# Motors.net
KiCad netlist of a schematic drawn in Altium Designer
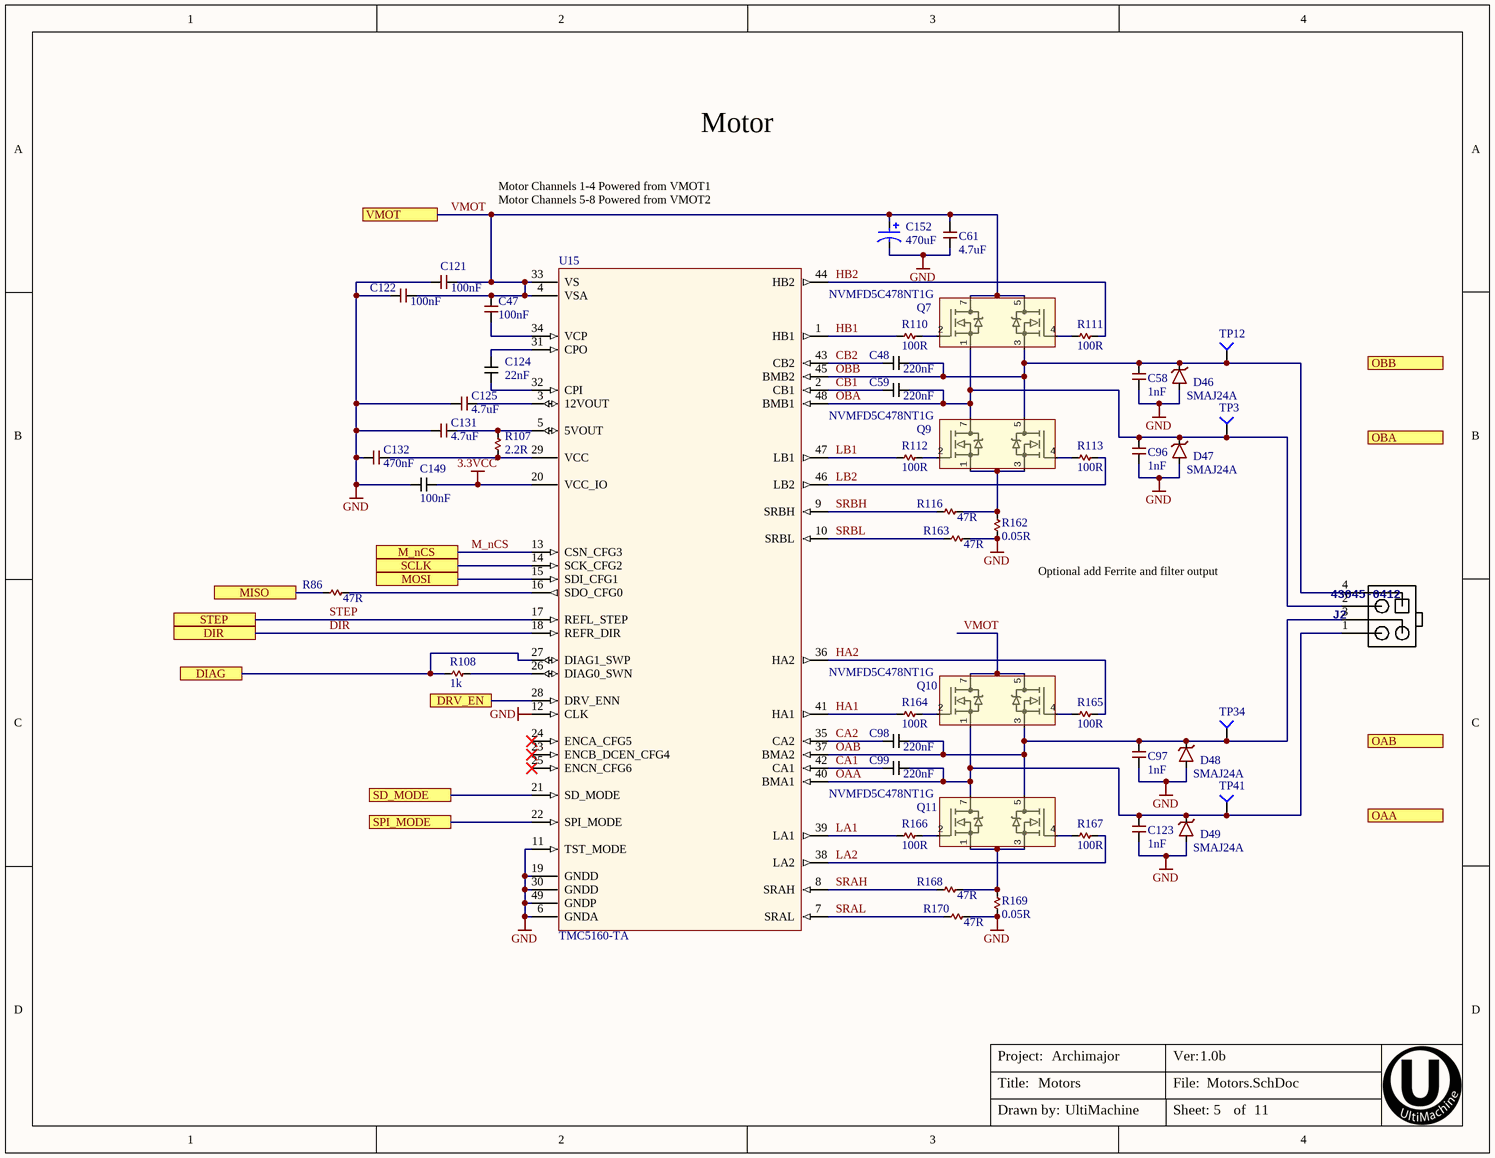
[diagram p0: Motors.SchDoc]

(export (version "E")
  (design (tool "Eeschema 10.0.6"))
  (components
    (comp (ref "C47")
      (value "100nF")
      (footprint "C0603")
      (description "CAP CER 0603 100nF 50V 10% X7R")
      (fields (field (name "MANUFACTURER") "Kemet") (field (name "PART") "C0603C104K5RACTU"))
      (libsource (lib "Capacitors") (part "100nF 0603 50V X7R"))
    )
    (comp (ref "C48")
      (value "220nF")
      (footprint "C0603")
      (description "CAP CER 0.22UF 50V X7R 0603")
      (fields (field (name "MANUFACTURER") "TDK") (field (name "PART") "CGA3E3X7R1H224K080AB"))
      (libsource (lib "Capacitors") (part "220nF 50V X7R 0603"))
    )
    (comp (ref "C58")
      (value "1nF")
      (footprint "C0603")
      (description "CAP CER 0603  1nF 50v 10% X7R")
      (fields (field (name "MANUFACTURER") "Kemet") (field (name "PART") "C0603C102K5RACTU"))
      (libsource (lib "Capacitors") (part "1nF 50V X7R 0603"))
    )
    (comp (ref "C59")
      (value "220nF")
      (footprint "C0603")
      (description "CAP CER 0.22UF 50V X7R 0603")
      (fields (field (name "MANUFACTURER") "TDK") (field (name "PART") "CGA3E3X7R1H224K080AB"))
      (libsource (lib "Capacitors") (part "220nF 50V X7R 0603"))
    )
    (comp (ref "C61")
      (value "4.7uF")
      (footprint "C1206")
      (description "CAP CER 1206 4.7uF 50V 10% X5R")
      (fields (field (name "MANUFACTURER") "Kemet") (field (name "PART") "C1206C475K5PACTU"))
      (libsource (lib "Capacitors") (part "4.7uF 1206 50V X5R"))
    )
    (comp (ref "C96")
      (value "1nF")
      (footprint "C0603")
      (description "CAP CER 0603  1nF 50v 10% X7R")
      (fields (field (name "MANUFACTURER") "Kemet") (field (name "PART") "C0603C102K5RACTU"))
      (libsource (lib "Capacitors") (part "1nF 50V X7R 0603"))
    )
    (comp (ref "C97")
      (value "1nF")
      (footprint "C0603")
      (description "CAP CER 0603  1nF 50v 10% X7R")
      (fields (field (name "MANUFACTURER") "Kemet") (field (name "PART") "C0603C102K5RACTU"))
      (libsource (lib "Capacitors") (part "1nF 50V X7R 0603"))
    )
    (comp (ref "C98")
      (value "220nF")
      (footprint "C0603")
      (description "CAP CER 0.22UF 50V X7R 0603")
      (fields (field (name "MANUFACTURER") "TDK") (field (name "PART") "CGA3E3X7R1H224K080AB"))
      (libsource (lib "Capacitors") (part "220nF 50V X7R 0603"))
    )
    (comp (ref "C99")
      (value "220nF")
      (footprint "C0603")
      (description "CAP CER 0.22UF 50V X7R 0603")
      (fields (field (name "MANUFACTURER") "TDK") (field (name "PART") "CGA3E3X7R1H224K080AB"))
      (libsource (lib "Capacitors") (part "220nF 50V X7R 0603"))
    )
    (comp (ref "C121")
      (value "100nF")
      (footprint "C0603")
      (description "CAP CER 0603 100nF 50V 10% X7R")
      (fields (field (name "MANUFACTURER") "Kemet") (field (name "PART") "C0603C104K5RACTU"))
      (libsource (lib "Capacitors") (part "100nF 0603 50V X7R"))
    )
    (comp (ref "C122")
      (value "100nF")
      (footprint "C0603")
      (description "CAP CER 0603 100nF 50V 10% X7R")
      (fields (field (name "MANUFACTURER") "Kemet") (field (name "PART") "C0603C104K5RACTU"))
      (libsource (lib "Capacitors") (part "100nF 0603 50V X7R"))
    )
    (comp (ref "C123")
      (value "1nF")
      (footprint "C0603")
      (description "CAP CER 0603  1nF 50v 10% X7R")
      (fields (field (name "MANUFACTURER") "Kemet") (field (name "PART") "C0603C102K5RACTU"))
      (libsource (lib "Capacitors") (part "1nF 50V X7R 0603"))
    )
    (comp (ref "C124")
      (value "22nF")
      (footprint "C0603")
      (description "CAP CER 0.022UF 100V X7R 0603")
      (fields (field (name "MANUFACTURER") "Kemet") (field (name "PART") "C0603C223K1RACTU"))
      (libsource (lib "Capacitors") (part "22nF 100V X7R 0603"))
    )
    (comp (ref "C125")
      (value "4.7uF")
      (footprint "C1206")
      (description "CAP CER 1206 4.7uF 50V 10% X5R")
      (fields (field (name "MANUFACTURER") "Kemet") (field (name "PART") "C1206C475K5PACTU"))
      (libsource (lib "Capacitors") (part "4.7uF 1206 50V X5R"))
    )
    (comp (ref "C131")
      (value "4.7uF")
      (footprint "C0603")
      (description "CAP CER 4.7UF 6.3V X7R 0603")
      (fields (field (name "MANUFACTURER") "Samsung") (field (name "PART") "CL10B475KQ8NQNC"))
      (libsource (lib "Capacitors") (part "4.7uF 0603 6.3V X7R"))
    )
    (comp (ref "C132")
      (value "470nF")
      (footprint "C0402")
      (description "470nF 6.3v C0402 - GRM155R60J474KE19D")
      (fields (field (name "TOLERANCE") "10%") (field (name "MANUFACTURER") "Murata"))
      (libsource (lib "Capacitors") (part "470nF 0402 6.3V X5R"))
    )
    (comp (ref "C149")
      (value "100nF")
      (footprint "C0201 Large Pads")
      (description "CAP CER 0.1UF 6.3V 10% X5R 0201")
      (fields (field (name "MANUFACTURER") "Samsung") (field (name "TOLERANCE") "10%"))
      (libsource (lib "Capacitors") (part "100nF 6.3V X5R 0201"))
    )
    (comp (ref "C152")
      (value "470uF")
      (footprint "CAP16x17")
      (description "CAP ALUM 470UF 20% 50V SMD")
      (fields (field (name "MANUFACTURER") "Nichicon") (field (name "PART") "UCZ1H471MNQ1MS"))
      (libsource (lib "Capacitors") (part "470uF Al-El 50V 80mOhms 16-18mmD"))
    )
    (comp (ref "D46")
      (value "SMAJ24A")
      (footprint "SMA-SM")
      (description "TVS DIODE 24V 38.9V SMA")
      (fields (field (name "MANUFACTURER") "Bourns Inc"))
      (libsource (lib "Diodes") (part "SMAJ24A"))
    )
    (comp (ref "D47")
      (value "SMAJ24A")
      (footprint "SMA-SM")
      (description "TVS DIODE 24V 38.9V SMA")
      (fields (field (name "MANUFACTURER") "Bourns Inc"))
      (libsource (lib "Diodes") (part "SMAJ24A"))
    )
    (comp (ref "D48")
      (value "SMAJ24A")
      (footprint "SMA-SM")
      (description "TVS DIODE 24V 38.9V SMA")
      (fields (field (name "MANUFACTURER") "Bourns Inc"))
      (libsource (lib "Diodes") (part "SMAJ24A"))
    )
    (comp (ref "D49")
      (value "SMAJ24A")
      (footprint "SMA-SM")
      (description "TVS DIODE 24V 38.9V SMA")
      (fields (field (name "MANUFACTURER") "Bourns Inc"))
      (libsource (lib "Diodes") (part "SMAJ24A"))
    )
    (comp (ref "J2")
      (value "43045-0412")
      (footprint "43045-0412")
      (description "Conn - 3mm Pitch Fixed")
      (fields (field (name "MANUFACTURER") "Molex"))
      (libsource (lib "Connectors") (part "Micro-Fit THT 4pos 3mm"))
    )
    (comp (ref "Q7")
      (value "NVMFD5C478NT1G")
      (footprint "SO8FL-Dual (DFN8 5x6, 1.26P Dual Flag)")
      (description "40V 17 MOHM T6 S08FL DUAL")
      (fields (field (name "MANUFACTURER") "ON Semiconductor") (field (name "TOLERANCE") "-NA-"))
      (libsource (lib "Transistors") (part "NVMFD5C478NT1G"))
    )
    (comp (ref "Q9")
      (value "NVMFD5C478NT1G")
      (footprint "SO8FL-Dual (DFN8 5x6, 1.26P Dual Flag)")
      (description "40V 17 MOHM T6 S08FL DUAL")
      (fields (field (name "MANUFACTURER") "ON Semiconductor") (field (name "TOLERANCE") "-NA-"))
      (libsource (lib "Transistors") (part "NVMFD5C478NT1G"))
    )
    (comp (ref "Q10")
      (value "NVMFD5C478NT1G")
      (footprint "SO8FL-Dual (DFN8 5x6, 1.26P Dual Flag)")
      (description "40V 17 MOHM T6 S08FL DUAL")
      (fields (field (name "MANUFACTURER") "ON Semiconductor") (field (name "TOLERANCE") "-NA-"))
      (libsource (lib "Transistors") (part "NVMFD5C478NT1G"))
    )
    (comp (ref "Q11")
      (value "NVMFD5C478NT1G")
      (footprint "SO8FL-Dual (DFN8 5x6, 1.26P Dual Flag)")
      (description "40V 17 MOHM T6 S08FL DUAL")
      (fields (field (name "MANUFACTURER") "ON Semiconductor") (field (name "TOLERANCE") "-NA-"))
      (libsource (lib "Transistors") (part "NVMFD5C478NT1G"))
    )
    (comp (ref "R86")
      (value "47R")
      (footprint "R0402")
      (description "RES 47 OHM 1% 1/16W 0402")
      (fields (field (name "MANUFACTURER") "Vishay Dale") (field (name "TOLERANCE") "+/- 1%"))
      (libsource (lib "Resistors") (part "47R 1% 0402"))
    )
    (comp (ref "R107")
      (value "2.2R")
      (footprint "R0402")
      (description "RES SMD 2.2 OHM 5% 1/16W 0402")
      (fields (field (name "MANUFACTURER") "Yageo") (field (name "TOLERANCE") "+/- 5%"))
      (libsource (lib "Resistors") (part "2.2R 5% 0402"))
    )
    (comp (ref "R108")
      (value "1k")
      (footprint "R0402")
      (description "RES 0402 1k 63mW 1%")
      (fields (field (name "MANUFACTURER") "Yageo") (field (name "PART") "RC0402FR-071KL"))
      (libsource (lib "Resistors") (part "1k 1% 0402"))
    )
    (comp (ref "R110")
      (value "100R")
      (footprint "R0402")
      (description "RES SMD 100 OHM 1% 1/16W 0402")
      (fields (field (name "MANUFACTURER") "Yageo") (field (name "PART") "100R 1% 0402"))
      (libsource (lib "Resistors") (part "100R 1% 0402"))
    )
    (comp (ref "R111")
      (value "100R")
      (footprint "R0402")
      (description "RES SMD 100 OHM 1% 1/16W 0402")
      (fields (field (name "MANUFACTURER") "Yageo") (field (name "PART") "100R 1% 0402"))
      (libsource (lib "Resistors") (part "100R 1% 0402"))
    )
    (comp (ref "R112")
      (value "100R")
      (footprint "R0402")
      (description "RES SMD 100 OHM 1% 1/16W 0402")
      (fields (field (name "MANUFACTURER") "Yageo") (field (name "PART") "100R 1% 0402"))
      (libsource (lib "Resistors") (part "100R 1% 0402"))
    )
    (comp (ref "R113")
      (value "100R")
      (footprint "R0402")
      (description "RES SMD 100 OHM 1% 1/16W 0402")
      (fields (field (name "MANUFACTURER") "Yageo") (field (name "PART") "100R 1% 0402"))
      (libsource (lib "Resistors") (part "100R 1% 0402"))
    )
    (comp (ref "R116")
      (value "47R")
      (footprint "R0402")
      (description "RES 47 OHM 1% 1/16W 0402")
      (fields (field (name "MANUFACTURER") "Vishay Dale") (field (name "TOLERANCE") "+/- 1%"))
      (libsource (lib "Resistors") (part "47R 1% 0402"))
    )
    (comp (ref "R162")
      (value "0.05R")
      (footprint "R2512")
      (description "RES 0.05 OHM 1% 2W 2512")
      (fields (field (name "MANUFACTURER") "Stackpole") (field (name "TOLERANCE") "+/- 1%"))
      (libsource (lib "Resistors") (part "0.05R 1% 2512"))
    )
    (comp (ref "R163")
      (value "47R")
      (footprint "R0402")
      (description "RES 47 OHM 1% 1/16W 0402")
      (fields (field (name "MANUFACTURER") "Vishay Dale") (field (name "TOLERANCE") "+/- 1%"))
      (libsource (lib "Resistors") (part "47R 1% 0402"))
    )
    (comp (ref "R164")
      (value "100R")
      (footprint "R0402")
      (description "RES SMD 100 OHM 1% 1/16W 0402")
      (fields (field (name "MANUFACTURER") "Yageo") (field (name "PART") "100R 1% 0402"))
      (libsource (lib "Resistors") (part "100R 1% 0402"))
    )
    (comp (ref "R165")
      (value "100R")
      (footprint "R0402")
      (description "RES SMD 100 OHM 1% 1/16W 0402")
      (fields (field (name "MANUFACTURER") "Yageo") (field (name "PART") "100R 1% 0402"))
      (libsource (lib "Resistors") (part "100R 1% 0402"))
    )
    (comp (ref "R166")
      (value "100R")
      (footprint "R0402")
      (description "RES SMD 100 OHM 1% 1/16W 0402")
      (fields (field (name "MANUFACTURER") "Yageo") (field (name "PART") "100R 1% 0402"))
      (libsource (lib "Resistors") (part "100R 1% 0402"))
    )
    (comp (ref "R167")
      (value "100R")
      (footprint "R0402")
      (description "RES SMD 100 OHM 1% 1/16W 0402")
      (fields (field (name "MANUFACTURER") "Yageo") (field (name "PART") "100R 1% 0402"))
      (libsource (lib "Resistors") (part "100R 1% 0402"))
    )
    (comp (ref "R168")
      (value "47R")
      (footprint "R0402")
      (description "RES 47 OHM 1% 1/16W 0402")
      (fields (field (name "MANUFACTURER") "Vishay Dale") (field (name "TOLERANCE") "+/- 1%"))
      (libsource (lib "Resistors") (part "47R 1% 0402"))
    )
    (comp (ref "R169")
      (value "0.05R")
      (footprint "R2512")
      (description "RES 0.05 OHM 1% 2W 2512")
      (fields (field (name "MANUFACTURER") "Stackpole") (field (name "TOLERANCE") "+/- 1%"))
      (libsource (lib "Resistors") (part "0.05R 1% 2512"))
    )
    (comp (ref "R170")
      (value "47R")
      (footprint "R0402")
      (description "RES 47 OHM 1% 1/16W 0402")
      (fields (field (name "MANUFACTURER") "Vishay Dale") (field (name "TOLERANCE") "+/- 1%"))
      (libsource (lib "Resistors") (part "47R 1% 0402"))
    )
    (comp (ref "TP3")
      (value "TP4")
      (footprint "TP-2")
      (description "Socket")
      (fields (field (name "PART") "NOTAPART-Testpoint"))
      (libsource (lib "Archim") (part "Socket"))
    )
    (comp (ref "TP12")
      (value "TP4")
      (footprint "TP-2")
      (description "Socket")
      (fields (field (name "PART") "NOTAPART-Testpoint"))
      (libsource (lib "Archim") (part "Socket"))
    )
    (comp (ref "TP34")
      (value "TP4")
      (footprint "TP-2")
      (description "Socket")
      (fields (field (name "PART") "NOTAPART-Testpoint"))
      (libsource (lib "Archim") (part "Socket"))
    )
    (comp (ref "TP41")
      (value "TP4")
      (footprint "TP-2")
      (description "Socket")
      (fields (field (name "PART") "NOTAPART-Testpoint"))
      (libsource (lib "Archim") (part "Socket"))
    )
    (comp (ref "U15")
      (value "TMC5160-TA")
      (footprint "TQFP48-EP")
      (description "IC STEPPER MOTOR DVR TQFP48-EP")
      (fields (field (name "MANUFACTURER") "Trinamic"))
      (libsource (lib "ICs-Motor Controller") (part "TMC5160-TA"))
    )
  )
  (nets
    (net (code "1") (name "/CA1") (class "Default")
      (node (ref "C99") (pin "1") (pinfunction "1_1") (pintype "passive"))
      (node (ref "U15") (pin "42") (pinfunction "CA1_42") (pintype "input"))
    )
    (net (code "2") (name "/CA2") (class "Default")
      (node (ref "C98") (pin "1") (pinfunction "1_1") (pintype "passive"))
      (node (ref "U15") (pin "35") (pinfunction "CA2_35") (pintype "input"))
    )
    (net (code "3") (name "/CB1") (class "Default")
      (node (ref "C59") (pin "1") (pinfunction "1_1") (pintype "passive"))
      (node (ref "U15") (pin "2") (pinfunction "CB1_2") (pintype "input"))
    )
    (net (code "4") (name "/CB2") (class "Default")
      (node (ref "C48") (pin "1") (pinfunction "1_1") (pintype "passive"))
      (node (ref "U15") (pin "43") (pinfunction "CB2_43") (pintype "input"))
    )
    (net (code "5") (name "/DIAG") (class "Default")
      (node (ref "R108") (pin "2") (pinfunction "2_2") (pintype "passive"))
      (node (ref "U15") (pin "27") (pinfunction "DIAG1_SWP_27") (pintype "bidirectional"))
    )
    (net (code "6") (name "/DIR") (class "Default")
      (node (ref "U15") (pin "18") (pinfunction "REFR_DIR_18") (pintype "input"))
    )
    (net (code "7") (name "/DRV_EN") (class "Default")
      (node (ref "U15") (pin "28") (pinfunction "DRV_ENN_28") (pintype "input"))
    )
    (net (code "8") (name "/HA1") (class "Default")
      (node (ref "R164") (pin "1") (pinfunction "1_1") (pintype "passive"))
      (node (ref "U15") (pin "41") (pinfunction "HA1_41") (pintype "output"))
    )
    (net (code "9") (name "/HA2") (class "Default")
      (node (ref "R165") (pin "2") (pinfunction "2_2") (pintype "passive"))
      (node (ref "U15") (pin "36") (pinfunction "HA2_36") (pintype "output"))
    )
    (net (code "10") (name "/HB1") (class "Default")
      (node (ref "R110") (pin "1") (pinfunction "1_1") (pintype "passive"))
      (node (ref "U15") (pin "1") (pinfunction "HB1_1") (pintype "output"))
    )
    (net (code "11") (name "/HB2") (class "Default")
      (node (ref "R111") (pin "2") (pinfunction "2_2") (pintype "passive"))
      (node (ref "U15") (pin "44") (pinfunction "HB2_44") (pintype "output"))
    )
    (net (code "12") (name "/LA1") (class "Default")
      (node (ref "R166") (pin "1") (pinfunction "1_1") (pintype "passive"))
      (node (ref "U15") (pin "39") (pinfunction "LA1_39") (pintype "output"))
    )
    (net (code "13") (name "/LA2") (class "Default")
      (node (ref "R167") (pin "2") (pinfunction "2_2") (pintype "passive"))
      (node (ref "U15") (pin "38") (pinfunction "LA2_38") (pintype "output"))
    )
    (net (code "14") (name "/LB1") (class "Default")
      (node (ref "R112") (pin "1") (pinfunction "1_1") (pintype "passive"))
      (node (ref "U15") (pin "47") (pinfunction "LB1_47") (pintype "output"))
    )
    (net (code "15") (name "/LB2") (class "Default")
      (node (ref "R113") (pin "2") (pinfunction "2_2") (pintype "passive"))
      (node (ref "U15") (pin "46") (pinfunction "LB2_46") (pintype "output"))
    )
    (net (code "16") (name "/MISO") (class "Default")
      (node (ref "R86") (pin "1") (pinfunction "1_1") (pintype "passive"))
    )
    (net (code "17") (name "/MOSI") (class "Default")
      (node (ref "U15") (pin "15") (pinfunction "SDI_CFG1_15") (pintype "input"))
    )
    (net (code "18") (name "/M_nCS") (class "Default")
      (node (ref "U15") (pin "13") (pinfunction "CSN_CFG3_13") (pintype "input"))
    )
    (net (code "19") (name "/OAA") (class "Default")
      (node (ref "C123") (pin "2") (pinfunction "2_2") (pintype "passive"))
      (node (ref "C99") (pin "2") (pinfunction "2_2") (pintype "passive"))
      (node (ref "D49") (pin "K") (pinfunction "K_K") (pintype "passive"))
      (node (ref "J2") (pin "1") (pinfunction "4_1") (pintype "power_in"))
      (node (ref "Q10") (pin "1") (pinfunction "S2_1") (pintype "passive"))
      (node (ref "Q11") (pin "7") (pinfunction "D2_7") (pintype "passive"))
      (node (ref "TP41") (pin "1") (pinfunction "1_1") (pintype "passive"))
      (node (ref "U15") (pin "40") (pinfunction "BMA1_40") (pintype "input"))
    )
    (net (code "20") (name "/OAB") (class "Default")
      (node (ref "C97") (pin "2") (pinfunction "2_2") (pintype "passive"))
      (node (ref "C98") (pin "2") (pinfunction "2_2") (pintype "passive"))
      (node (ref "D48") (pin "K") (pinfunction "K_K") (pintype "passive"))
      (node (ref "J2") (pin "3") (pinfunction "3_3") (pintype "power_in"))
      (node (ref "Q10") (pin "3") (pinfunction "S1_3") (pintype "passive"))
      (node (ref "Q11") (pin "5") (pinfunction "D1_5") (pintype "passive"))
      (node (ref "TP34") (pin "1") (pinfunction "1_1") (pintype "passive"))
      (node (ref "U15") (pin "37") (pinfunction "BMA2_37") (pintype "input"))
    )
    (net (code "21") (name "/OBA") (class "Default")
      (node (ref "C59") (pin "2") (pinfunction "2_2") (pintype "passive"))
      (node (ref "C96") (pin "2") (pinfunction "2_2") (pintype "passive"))
      (node (ref "D47") (pin "K") (pinfunction "K_K") (pintype "passive"))
      (node (ref "J2") (pin "2") (pinfunction "2_2") (pintype "power_in"))
      (node (ref "Q7") (pin "1") (pinfunction "S2_1") (pintype "passive"))
      (node (ref "Q9") (pin "7") (pinfunction "D2_7") (pintype "passive"))
      (node (ref "TP3") (pin "1") (pinfunction "1_1") (pintype "passive"))
      (node (ref "U15") (pin "48") (pinfunction "BMB1_48") (pintype "input"))
    )
    (net (code "22") (name "/OBB") (class "Default")
      (node (ref "C48") (pin "2") (pinfunction "2_2") (pintype "passive"))
      (node (ref "C58") (pin "2") (pinfunction "2_2") (pintype "passive"))
      (node (ref "D46") (pin "K") (pinfunction "K_K") (pintype "passive"))
      (node (ref "J2") (pin "4") (pinfunction "1_4") (pintype "power_in"))
      (node (ref "Q7") (pin "3") (pinfunction "S1_3") (pintype "passive"))
      (node (ref "Q9") (pin "5") (pinfunction "D1_5") (pintype "passive"))
      (node (ref "TP12") (pin "1") (pinfunction "1_1") (pintype "passive"))
      (node (ref "U15") (pin "45") (pinfunction "BMB2_45") (pintype "input"))
    )
    (net (code "23") (name "/SCLK") (class "Default")
      (node (ref "U15") (pin "14") (pinfunction "SCK_CFG2_14") (pintype "input"))
    )
    (net (code "24") (name "/SD_MODE") (class "Default")
      (node (ref "U15") (pin "21") (pinfunction "SD_MODE_21") (pintype "input"))
    )
    (net (code "25") (name "/SPI_MODE") (class "Default")
      (node (ref "U15") (pin "22") (pinfunction "SPI_MODE_22") (pintype "input"))
    )
    (net (code "26") (name "/SRAH") (class "Default")
      (node (ref "R168") (pin "1") (pinfunction "1_1") (pintype "passive"))
      (node (ref "U15") (pin "8") (pinfunction "SRAH_8") (pintype "input"))
    )
    (net (code "27") (name "/SRAL") (class "Default")
      (node (ref "R170") (pin "1") (pinfunction "1_1") (pintype "passive"))
      (node (ref "U15") (pin "7") (pinfunction "SRAL_7") (pintype "input"))
    )
    (net (code "28") (name "/SRBH") (class "Default")
      (node (ref "R116") (pin "1") (pinfunction "1_1") (pintype "passive"))
      (node (ref "U15") (pin "9") (pinfunction "SRBH_9") (pintype "input"))
    )
    (net (code "29") (name "/SRBL") (class "Default")
      (node (ref "R163") (pin "1") (pinfunction "1_1") (pintype "passive"))
      (node (ref "U15") (pin "10") (pinfunction "SRBL_10") (pintype "input"))
    )
    (net (code "30") (name "/STEP") (class "Default")
      (node (ref "U15") (pin "17") (pinfunction "REFL_STEP_17") (pintype "input"))
    )
    (net (code "31") (name "/VMOT") (class "Default")
      (node (ref "C121") (pin "2") (pinfunction "2_2") (pintype "passive"))
      (node (ref "C122") (pin "2") (pinfunction "2_2") (pintype "passive"))
      (node (ref "C152") (pin "1") (pinfunction "1_1") (pintype "passive"))
      (node (ref "C47") (pin "2") (pinfunction "2_2") (pintype "passive"))
      (node (ref "C61") (pin "2") (pinfunction "2_2") (pintype "passive"))
      (node (ref "Q10") (pin "5") (pinfunction "D1_5") (pintype "passive"))
      (node (ref "Q10") (pin "7") (pinfunction "D2_7") (pintype "passive"))
      (node (ref "Q7") (pin "5") (pinfunction "D1_5") (pintype "passive"))
      (node (ref "Q7") (pin "7") (pinfunction "D2_7") (pintype "passive"))
      (node (ref "U15") (pin "33") (pinfunction "VS_33") (pintype "power_in"))
      (node (ref "U15") (pin "4") (pinfunction "VSA_4") (pintype "power_in"))
    )
    (net (code "32") (name "3.3VCC") (class "Default")
      (node (ref "C149") (pin "2") (pinfunction "2_2") (pintype "passive"))
      (node (ref "U15") (pin "20") (pinfunction "VCC_IO_20") (pintype "power_in"))
    )
    (net (code "33") (name "GND") (class "Default")
      (node (ref "C121") (pin "1") (pinfunction "1_1") (pintype "passive"))
      (node (ref "C122") (pin "1") (pinfunction "1_1") (pintype "passive"))
      (node (ref "C123") (pin "1") (pinfunction "1_1") (pintype "passive"))
      (node (ref "C125") (pin "1") (pinfunction "1_1") (pintype "passive"))
      (node (ref "C131") (pin "1") (pinfunction "1_1") (pintype "passive"))
      (node (ref "C132") (pin "1") (pinfunction "1_1") (pintype "passive"))
      (node (ref "C149") (pin "1") (pinfunction "1_1") (pintype "passive"))
      (node (ref "C152") (pin "2") (pinfunction "2_2") (pintype "passive"))
      (node (ref "C58") (pin "1") (pinfunction "1_1") (pintype "passive"))
      (node (ref "C61") (pin "1") (pinfunction "1_1") (pintype "passive"))
      (node (ref "C96") (pin "1") (pinfunction "1_1") (pintype "passive"))
      (node (ref "C97") (pin "1") (pinfunction "1_1") (pintype "passive"))
      (node (ref "D46") (pin "A") (pinfunction "A_A") (pintype "passive"))
      (node (ref "D47") (pin "A") (pinfunction "A_A") (pintype "passive"))
      (node (ref "D48") (pin "A") (pinfunction "A_A") (pintype "passive"))
      (node (ref "D49") (pin "A") (pinfunction "A_A") (pintype "passive"))
      (node (ref "R162") (pin "2") (pinfunction "2_2") (pintype "passive"))
      (node (ref "R163") (pin "2") (pinfunction "2_2") (pintype "passive"))
      (node (ref "R169") (pin "1") (pinfunction "1_1") (pintype "passive"))
      (node (ref "R170") (pin "2") (pinfunction "2_2") (pintype "passive"))
      (node (ref "U15") (pin "11") (pinfunction "TST_MODE_11") (pintype "input"))
      (node (ref "U15") (pin "12") (pinfunction "CLK_12") (pintype "input"))
      (node (ref "U15") (pin "19") (pinfunction "GNDD_19") (pintype "power_in"))
      (node (ref "U15") (pin "30") (pinfunction "GNDD_30") (pintype "power_in"))
      (node (ref "U15") (pin "49") (pinfunction "GNDP_49") (pintype "power_in"))
      (node (ref "U15") (pin "6") (pinfunction "GNDA_6") (pintype "power_in"))
    )
    (net (code "34") (name "Net-(Q7-G1)") (class "Default")
      (node (ref "Q7") (pin "4") (pinfunction "G1_4") (pintype "passive"))
      (node (ref "R111") (pin "1") (pinfunction "1_1") (pintype "passive"))
    )
    (net (code "35") (name "Net-(Q7-G2)") (class "Default")
      (node (ref "Q7") (pin "2") (pinfunction "G2_2") (pintype "passive"))
      (node (ref "R110") (pin "2") (pinfunction "2_2") (pintype "passive"))
    )
    (net (code "36") (name "Net-(Q9-G1)") (class "Default")
      (node (ref "Q9") (pin "4") (pinfunction "G1_4") (pintype "passive"))
      (node (ref "R113") (pin "1") (pinfunction "1_1") (pintype "passive"))
    )
    (net (code "37") (name "Net-(Q9-G2)") (class "Default")
      (node (ref "Q9") (pin "2") (pinfunction "G2_2") (pintype "passive"))
      (node (ref "R112") (pin "2") (pinfunction "2_2") (pintype "passive"))
    )
    (net (code "38") (name "Net-(Q9-S1)") (class "Default")
      (node (ref "Q9") (pin "1") (pinfunction "S2_1") (pintype "passive"))
      (node (ref "Q9") (pin "3") (pinfunction "S1_3") (pintype "passive"))
      (node (ref "R116") (pin "2") (pinfunction "2_2") (pintype "passive"))
      (node (ref "R162") (pin "1") (pinfunction "1_1") (pintype "passive"))
    )
    (net (code "39") (name "Net-(Q10-G1)") (class "Default")
      (node (ref "Q10") (pin "4") (pinfunction "G1_4") (pintype "passive"))
      (node (ref "R165") (pin "1") (pinfunction "1_1") (pintype "passive"))
    )
    (net (code "40") (name "Net-(Q10-G2)") (class "Default")
      (node (ref "Q10") (pin "2") (pinfunction "G2_2") (pintype "passive"))
      (node (ref "R164") (pin "2") (pinfunction "2_2") (pintype "passive"))
    )
    (net (code "41") (name "Net-(Q11-G1)") (class "Default")
      (node (ref "Q11") (pin "4") (pinfunction "G1_4") (pintype "passive"))
      (node (ref "R167") (pin "1") (pinfunction "1_1") (pintype "passive"))
    )
    (net (code "42") (name "Net-(Q11-G2)") (class "Default")
      (node (ref "Q11") (pin "2") (pinfunction "G2_2") (pintype "passive"))
      (node (ref "R166") (pin "2") (pinfunction "2_2") (pintype "passive"))
    )
    (net (code "43") (name "Net-(Q11-S1)") (class "Default")
      (node (ref "Q11") (pin "1") (pinfunction "S2_1") (pintype "passive"))
      (node (ref "Q11") (pin "3") (pinfunction "S1_3") (pintype "passive"))
      (node (ref "R168") (pin "2") (pinfunction "2_2") (pintype "passive"))
      (node (ref "R169") (pin "2") (pinfunction "2_2") (pintype "passive"))
    )
    (net (code "44") (name "Net-(U15-5VOUT)") (class "Default")
      (node (ref "C131") (pin "2") (pinfunction "2_2") (pintype "passive"))
      (node (ref "R107") (pin "2") (pinfunction "2_2") (pintype "passive"))
      (node (ref "U15") (pin "5") (pinfunction "5VOUT_5") (pintype "bidirectional"))
    )
    (net (code "45") (name "Net-(U15-12VOUT)") (class "Default")
      (node (ref "C125") (pin "2") (pinfunction "2_2") (pintype "passive"))
      (node (ref "U15") (pin "3") (pinfunction "12VOUT_3") (pintype "bidirectional"))
    )
    (net (code "46") (name "Net-(U15-CPI)") (class "Default")
      (node (ref "C124") (pin "1") (pinfunction "1_1") (pintype "passive"))
      (node (ref "U15") (pin "32") (pinfunction "CPI_32") (pintype "input"))
    )
    (net (code "47") (name "Net-(U15-CPO)") (class "Default")
      (node (ref "C124") (pin "2") (pinfunction "2_2") (pintype "passive"))
      (node (ref "U15") (pin "31") (pinfunction "CPO_31") (pintype "input"))
    )
    (net (code "48") (name "Net-(U15-DIAG0_SWN)") (class "Default")
      (node (ref "R108") (pin "1") (pinfunction "1_1") (pintype "passive"))
      (node (ref "U15") (pin "26") (pinfunction "DIAG0_SWN_26") (pintype "bidirectional"))
    )
    (net (code "49") (name "Net-(U15-SDO_CFG0)") (class "Default")
      (node (ref "R86") (pin "2") (pinfunction "2_2") (pintype "passive"))
      (node (ref "U15") (pin "16") (pinfunction "SDO_CFG0_16") (pintype "output"))
    )
    (net (code "50") (name "Net-(U15-VCC)") (class "Default")
      (node (ref "C132") (pin "2") (pinfunction "2_2") (pintype "passive"))
      (node (ref "R107") (pin "1") (pinfunction "1_1") (pintype "passive"))
      (node (ref "U15") (pin "29") (pinfunction "VCC_29") (pintype "power_in"))
    )
    (net (code "51") (name "Net-(U15-VCP)") (class "Default")
      (node (ref "C47") (pin "1") (pinfunction "1_1") (pintype "passive"))
      (node (ref "U15") (pin "34") (pinfunction "VCP_34") (pintype "input"))
    )
    (net (code "52") (name "unconnected-(U15-ENCA_CFG5-Pad24)") (class "Default")
      (node (ref "U15") (pin "24") (pinfunction "ENCA_CFG5_24") (pintype "input+no_connect"))
    )
    (net (code "53") (name "unconnected-(U15-ENCB_DCEN_CFG4-Pad23)") (class "Default")
      (node (ref "U15") (pin "23") (pinfunction "ENCB_DCEN_CFG4_23") (pintype "input+no_connect"))
    )
    (net (code "54") (name "unconnected-(U15-ENCN_CFG6-Pad25)") (class "Default")
      (node (ref "U15") (pin "25") (pinfunction "ENCN_CFG6_25") (pintype "input+no_connect"))
    )
  )
)
